# arduino_isp_shield.net
KiCad netlist of a schematic drawn in EAGLE
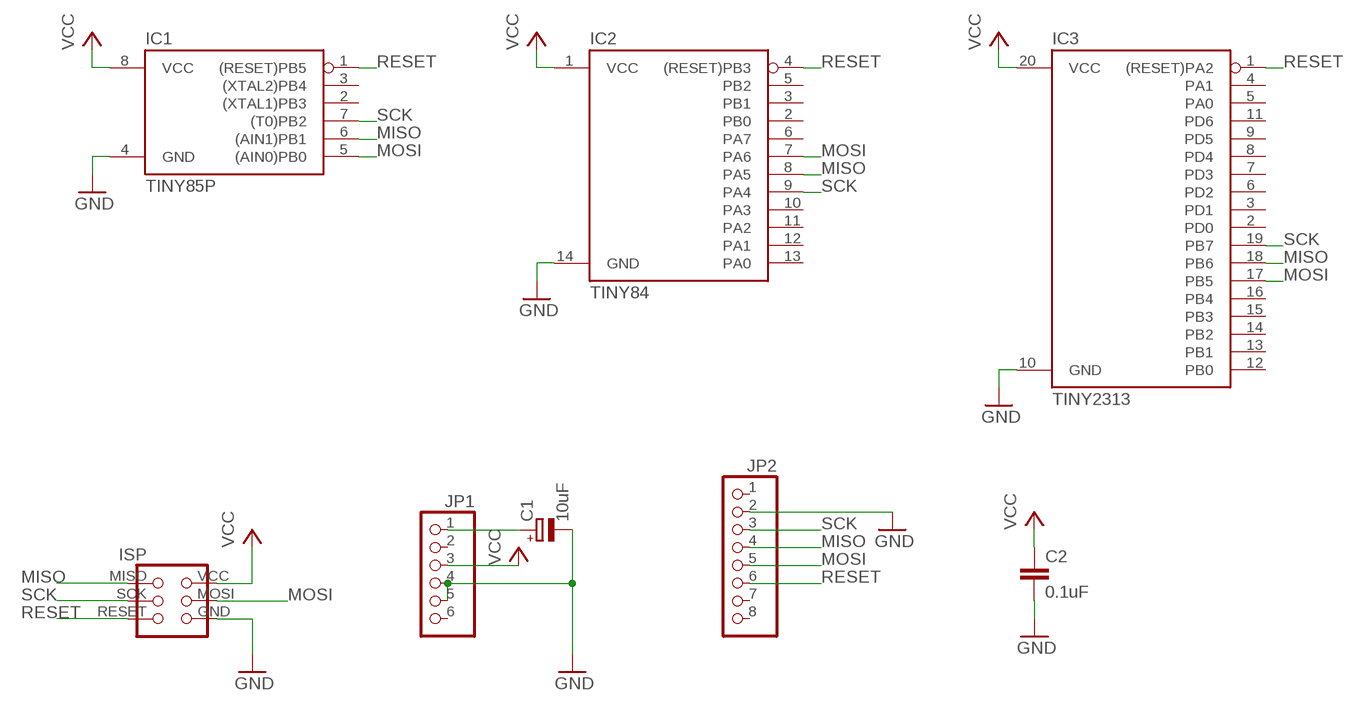
[diagram p0: schematic, sheet 1]

(export (version "E")
  (design (tool "Eeschema 10.0.6"))
  (components
    (comp (ref "C1")
      (value "10uF")
      (footprint "eagle-import:E1,8-4")
      (libsource (lib "eagle-import") (part "CPOL-EUE1.8-4"))
    )
    (comp (ref "C2")
      (value "0.1uF")
      (footprint "eagle-import:C050-025X075")
      (libsource (lib "eagle-import") (part "C-EU050-025X075"))
    )
    (comp (ref "IC1")
      (value "TINY85P")
      (footprint "eagle-import:DIL08")
      (libsource (lib "eagle-import") (part "TINY85P"))
    )
    (comp (ref "IC2")
      (value "TINY84")
      (footprint "eagle-import:DIL14")
      (libsource (lib "eagle-import") (part "TINY84"))
    )
    (comp (ref "IC3")
      (value "TINY2313")
      (footprint "eagle-import:DIL20")
      (libsource (lib "eagle-import") (part "TINY2313"))
    )
    (comp (ref "ISP")
      (value "AVR-ISP")
      (footprint "eagle-import:AVR-ISP")
      (libsource (lib "eagle-import") (part "AVR-ISP"))
    )
    (comp (ref "JP1")
      (value "PINHD-1X6")
      (footprint "eagle-import:1X06")
      (libsource (lib "eagle-import") (part "PINHD-1X6"))
    )
    (comp (ref "JP2")
      (value "PINHD-1X8")
      (footprint "eagle-import:1X08")
      (libsource (lib "eagle-import") (part "PINHD-1X8"))
    )
  )
  (nets
    (net (code "1") (name "/MISO") (class "Default")
      (node (ref "IC1") (pin "6") (pinfunction "(AIN1)PB1_6") (pintype "bidirectional"))
      (node (ref "IC2") (pin "8") (pinfunction "PA5_8") (pintype "bidirectional"))
      (node (ref "IC3") (pin "18") (pinfunction "PB6_18") (pintype "bidirectional"))
      (node (ref "ISP") (pin "MISO") (pinfunction "MISO_MISO") (pintype "bidirectional"))
      (node (ref "JP2") (pin "4") (pinfunction "4_4") (pintype "passive"))
    )
    (net (code "2") (name "/MOSI") (class "Default")
      (node (ref "IC1") (pin "5") (pinfunction "(AIN0)PB0_5") (pintype "bidirectional"))
      (node (ref "IC2") (pin "7") (pinfunction "PA6_7") (pintype "bidirectional"))
      (node (ref "IC3") (pin "17") (pinfunction "PB5_17") (pintype "bidirectional"))
      (node (ref "ISP") (pin "MOSI") (pinfunction "MOSI_MOSI") (pintype "bidirectional"))
      (node (ref "JP2") (pin "5") (pinfunction "5_5") (pintype "passive"))
    )
    (net (code "3") (name "/RESET") (class "Default")
      (node (ref "IC1") (pin "1") (pinfunction "(RESET)PB5_1") (pintype "bidirectional"))
      (node (ref "IC2") (pin "4") (pinfunction "(RESET)PB3_4") (pintype "bidirectional"))
      (node (ref "IC3") (pin "1") (pinfunction "(RESET)PA2_1") (pintype "bidirectional"))
      (node (ref "ISP") (pin "RESET") (pinfunction "RESET_RESET") (pintype "bidirectional"))
      (node (ref "JP2") (pin "6") (pinfunction "6_6") (pintype "passive"))
    )
    (net (code "4") (name "/SCK") (class "Default")
      (node (ref "IC1") (pin "7") (pinfunction "(T0)PB2_7") (pintype "bidirectional"))
      (node (ref "IC2") (pin "9") (pinfunction "PA4_9") (pintype "bidirectional"))
      (node (ref "IC3") (pin "19") (pinfunction "PB7_19") (pintype "bidirectional"))
      (node (ref "ISP") (pin "SCK") (pinfunction "SCK_SCK") (pintype "bidirectional"))
      (node (ref "JP2") (pin "3") (pinfunction "3_3") (pintype "passive"))
    )
    (net (code "5") (name "GND") (class "Default")
      (node (ref "C1") (pin "-") (pinfunction "-_-") (pintype "passive"))
      (node (ref "C2") (pin "2") (pinfunction "2_2") (pintype "passive"))
      (node (ref "IC1") (pin "4") (pinfunction "GND_4") (pintype "power_in"))
      (node (ref "IC2") (pin "14") (pinfunction "GND_14") (pintype "power_in"))
      (node (ref "IC3") (pin "10") (pinfunction "GND_10") (pintype "power_in"))
      (node (ref "ISP") (pin "GND") (pinfunction "GND_GND") (pintype "power_in"))
      (node (ref "JP1") (pin "4") (pinfunction "4_4") (pintype "passive"))
      (node (ref "JP1") (pin "5") (pinfunction "5_5") (pintype "passive"))
      (node (ref "JP2") (pin "2") (pinfunction "2_2") (pintype "passive"))
    )
    (net (code "6") (name "Net-(C1-Pad+)") (class "Default")
      (node (ref "C1") (pin "+") (pinfunction "+_+") (pintype "passive"))
      (node (ref "JP1") (pin "1") (pinfunction "1_1") (pintype "passive"))
    )
    (net (code "7") (name "VCC") (class "Default")
      (node (ref "C2") (pin "1") (pinfunction "1_1") (pintype "passive"))
      (node (ref "IC1") (pin "8") (pinfunction "VCC_8") (pintype "power_in"))
      (node (ref "IC2") (pin "1") (pinfunction "VCC_1") (pintype "power_in"))
      (node (ref "IC3") (pin "20") (pinfunction "VCC_20") (pintype "power_in"))
      (node (ref "ISP") (pin "VCC") (pinfunction "VCC_VCC") (pintype "power_in"))
      (node (ref "JP1") (pin "3") (pinfunction "3_3") (pintype "passive"))
    )
    (net (code "8") (name "unconnected-(IC1-(XTAL1)PB3-Pad2)") (class "Default")
      (node (ref "IC1") (pin "2") (pinfunction "(XTAL1)PB3_2") (pintype "bidirectional"))
    )
    (net (code "9") (name "unconnected-(IC1-(XTAL2)PB4-Pad3)") (class "Default")
      (node (ref "IC1") (pin "3") (pinfunction "(XTAL2)PB4_3") (pintype "bidirectional"))
    )
    (net (code "10") (name "unconnected-(IC2-PA0-Pad13)") (class "Default")
      (node (ref "IC2") (pin "13") (pinfunction "PA0_13") (pintype "bidirectional"))
    )
    (net (code "11") (name "unconnected-(IC2-PA1-Pad12)") (class "Default")
      (node (ref "IC2") (pin "12") (pinfunction "PA1_12") (pintype "bidirectional"))
    )
    (net (code "12") (name "unconnected-(IC2-PA2-Pad11)") (class "Default")
      (node (ref "IC2") (pin "11") (pinfunction "PA2_11") (pintype "bidirectional"))
    )
    (net (code "13") (name "unconnected-(IC2-PA3-Pad10)") (class "Default")
      (node (ref "IC2") (pin "10") (pinfunction "PA3_10") (pintype "bidirectional"))
    )
    (net (code "14") (name "unconnected-(IC2-PA7-Pad6)") (class "Default")
      (node (ref "IC2") (pin "6") (pinfunction "PA7_6") (pintype "bidirectional"))
    )
    (net (code "15") (name "unconnected-(IC2-PB0-Pad2)") (class "Default")
      (node (ref "IC2") (pin "2") (pinfunction "PB0_2") (pintype "bidirectional"))
    )
    (net (code "16") (name "unconnected-(IC2-PB1-Pad3)") (class "Default")
      (node (ref "IC2") (pin "3") (pinfunction "PB1_3") (pintype "bidirectional"))
    )
    (net (code "17") (name "unconnected-(IC2-PB2-Pad5)") (class "Default")
      (node (ref "IC2") (pin "5") (pinfunction "PB2_5") (pintype "bidirectional"))
    )
    (net (code "18") (name "unconnected-(IC3-PA0-Pad5)") (class "Default")
      (node (ref "IC3") (pin "5") (pinfunction "PA0_5") (pintype "bidirectional"))
    )
    (net (code "19") (name "unconnected-(IC3-PA1-Pad4)") (class "Default")
      (node (ref "IC3") (pin "4") (pinfunction "PA1_4") (pintype "bidirectional"))
    )
    (net (code "20") (name "unconnected-(IC3-PB0-Pad12)") (class "Default")
      (node (ref "IC3") (pin "12") (pinfunction "PB0_12") (pintype "bidirectional"))
    )
    (net (code "21") (name "unconnected-(IC3-PB1-Pad13)") (class "Default")
      (node (ref "IC3") (pin "13") (pinfunction "PB1_13") (pintype "bidirectional"))
    )
    (net (code "22") (name "unconnected-(IC3-PB2-Pad14)") (class "Default")
      (node (ref "IC3") (pin "14") (pinfunction "PB2_14") (pintype "bidirectional"))
    )
    (net (code "23") (name "unconnected-(IC3-PB3-Pad15)") (class "Default")
      (node (ref "IC3") (pin "15") (pinfunction "PB3_15") (pintype "bidirectional"))
    )
    (net (code "24") (name "unconnected-(IC3-PB4-Pad16)") (class "Default")
      (node (ref "IC3") (pin "16") (pinfunction "PB4_16") (pintype "bidirectional"))
    )
    (net (code "25") (name "unconnected-(IC3-PD0-Pad2)") (class "Default")
      (node (ref "IC3") (pin "2") (pinfunction "PD0_2") (pintype "bidirectional"))
    )
    (net (code "26") (name "unconnected-(IC3-PD1-Pad3)") (class "Default")
      (node (ref "IC3") (pin "3") (pinfunction "PD1_3") (pintype "bidirectional"))
    )
    (net (code "27") (name "unconnected-(IC3-PD2-Pad6)") (class "Default")
      (node (ref "IC3") (pin "6") (pinfunction "PD2_6") (pintype "bidirectional"))
    )
    (net (code "28") (name "unconnected-(IC3-PD3-Pad7)") (class "Default")
      (node (ref "IC3") (pin "7") (pinfunction "PD3_7") (pintype "bidirectional"))
    )
    (net (code "29") (name "unconnected-(IC3-PD4-Pad8)") (class "Default")
      (node (ref "IC3") (pin "8") (pinfunction "PD4_8") (pintype "bidirectional"))
    )
    (net (code "30") (name "unconnected-(IC3-PD5-Pad9)") (class "Default")
      (node (ref "IC3") (pin "9") (pinfunction "PD5_9") (pintype "bidirectional"))
    )
    (net (code "31") (name "unconnected-(IC3-PD6-Pad11)") (class "Default")
      (node (ref "IC3") (pin "11") (pinfunction "PD6_11") (pintype "bidirectional"))
    )
    (net (code "32") (name "unconnected-(JP1-Pad2)") (class "Default")
      (node (ref "JP1") (pin "2") (pinfunction "2_2") (pintype "passive"))
    )
    (net (code "33") (name "unconnected-(JP1-Pad6)") (class "Default")
      (node (ref "JP1") (pin "6") (pinfunction "6_6") (pintype "passive"))
    )
    (net (code "34") (name "unconnected-(JP2-Pad1)") (class "Default")
      (node (ref "JP2") (pin "1") (pinfunction "1_1") (pintype "passive"))
    )
    (net (code "35") (name "unconnected-(JP2-Pad7)") (class "Default")
      (node (ref "JP2") (pin "7") (pinfunction "7_7") (pintype "passive"))
    )
    (net (code "36") (name "unconnected-(JP2-Pad8)") (class "Default")
      (node (ref "JP2") (pin "8") (pinfunction "8_8") (pintype "passive"))
    )
  )
)
